# PowerSheet1.net
KiCad netlist of a schematic drawn in Altium Designer
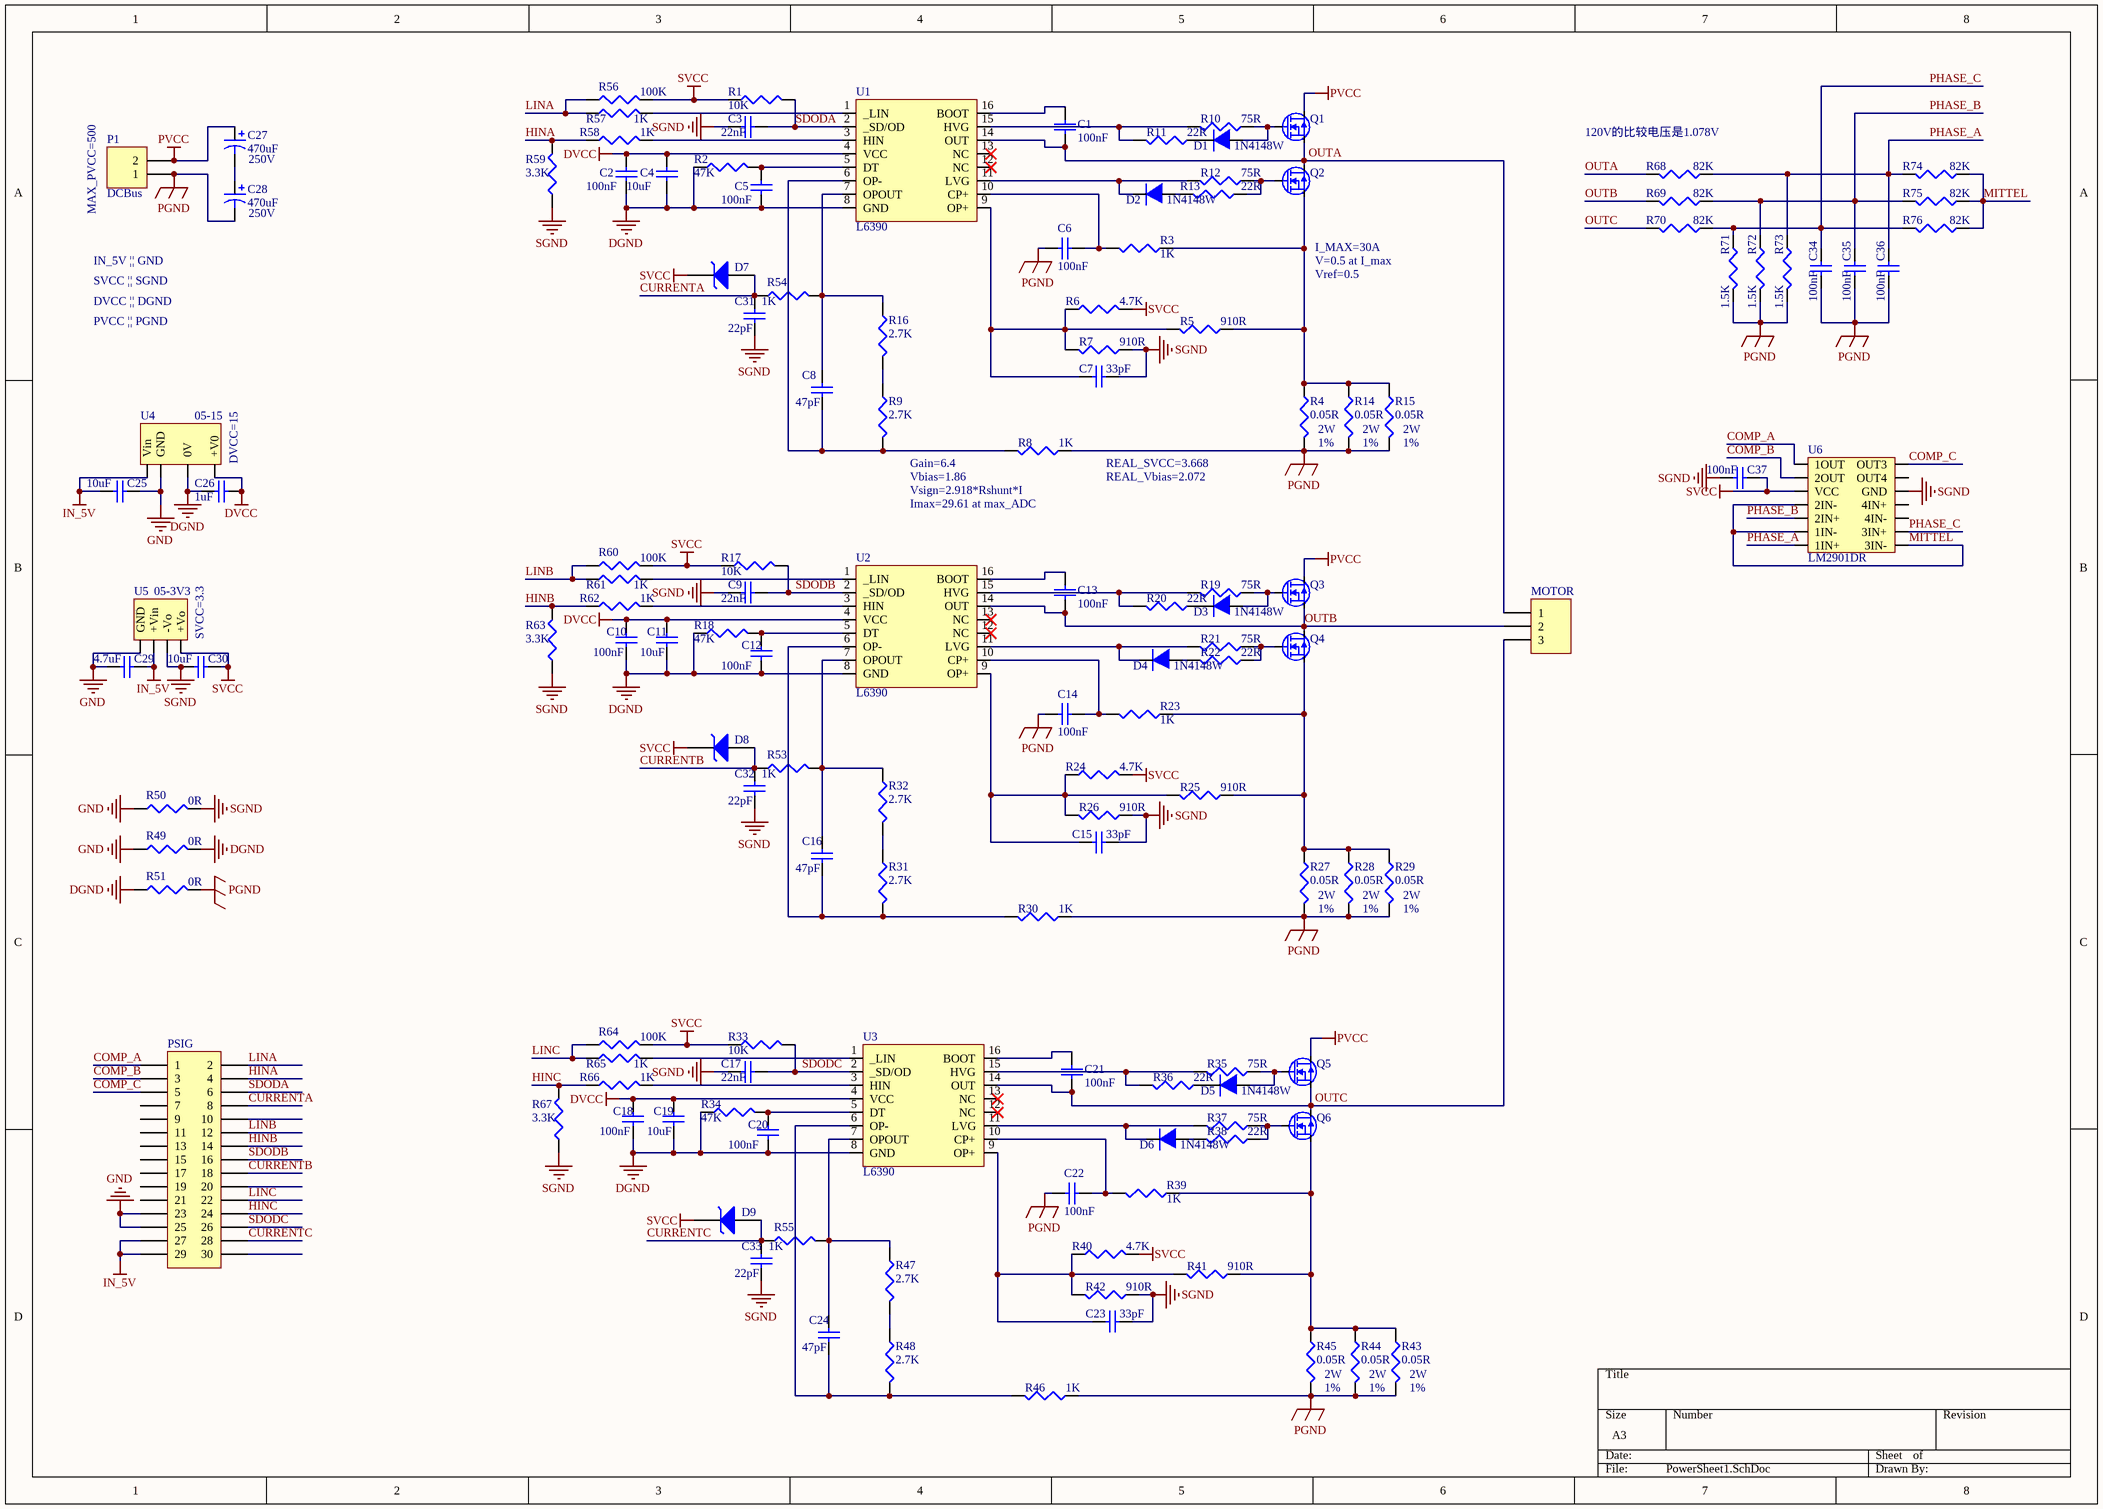
[diagram p0: PowerSheet1.SchDoc]

(export (version "E")
  (design (tool "Eeschema 10.0.6"))
  (components
    (comp (ref "C1")
      (value "100nF")
      (footprint "LC-1210_C")
      (description "Capacitor (Semiconductor SIM Model)")
      (fields (field (name "Comment") "Cap Semi") (field (name "PUBLISHER") "Altium Limited"))
      (libsource (lib "Miscellaneous Devices") (part "Cap Semi"))
    )
    (comp (ref "C2")
      (value "100nF")
      (footprint "LC-0805_C")
      (description "Capacitor (Semiconductor SIM Model)")
      (fields (field (name "Comment") "Cap Semi") (field (name "PUBLISHER") "Altium Limited"))
      (libsource (lib "Miscellaneous Devices") (part "Cap Semi"))
    )
    (comp (ref "C3")
      (value "22nF")
      (footprint "LC-0805_C")
      (description "Capacitor (Semiconductor SIM Model)")
      (fields (field (name "Comment") "Cap Semi") (field (name "PUBLISHER") "Altium Limited"))
      (libsource (lib "Miscellaneous Devices") (part "Cap Semi"))
    )
    (comp (ref "C4")
      (value "10uF")
      (footprint "LC-0805_C")
      (description "Capacitor (Semiconductor SIM Model)")
      (fields (field (name "Comment") "Cap Semi") (field (name "PUBLISHER") "Altium Limited"))
      (libsource (lib "Miscellaneous Devices") (part "Cap Semi"))
    )
    (comp (ref "C5")
      (value "100nF")
      (footprint "LC-0805_C")
      (description "Capacitor (Semiconductor SIM Model)")
      (fields (field (name "Comment") "Cap Semi") (field (name "PUBLISHER") "Altium Limited"))
      (libsource (lib "Miscellaneous Devices") (part "Cap Semi"))
    )
    (comp (ref "C6")
      (value "100nF")
      (footprint "LC-0805_C")
      (description "Capacitor (Semiconductor SIM Model)")
      (fields (field (name "Comment") "Cap Semi") (field (name "PUBLISHER") "Altium Limited"))
      (libsource (lib "Miscellaneous Devices") (part "Cap Semi"))
    )
    (comp (ref "C7")
      (value "33pF")
      (footprint "LC-0805_C")
      (description "Capacitor (Semiconductor SIM Model)")
      (fields (field (name "Comment") "Cap Semi") (field (name "PUBLISHER") "Altium Limited"))
      (libsource (lib "Miscellaneous Devices") (part "Cap Semi"))
    )
    (comp (ref "C8")
      (value "47pF")
      (footprint "LC-0805_C")
      (description "Capacitor (Semiconductor SIM Model)")
      (fields (field (name "Comment") "Cap Semi") (field (name "PUBLISHER") "Altium Limited"))
      (libsource (lib "Miscellaneous Devices") (part "Cap Semi"))
    )
    (comp (ref "C9")
      (value "22nF")
      (footprint "LC-0805_C")
      (description "Capacitor (Semiconductor SIM Model)")
      (fields (field (name "Comment") "Cap Semi") (field (name "PUBLISHER") "Altium Limited"))
      (libsource (lib "Miscellaneous Devices") (part "Cap Semi"))
    )
    (comp (ref "C10")
      (value "100nF")
      (footprint "LC-0805_C")
      (description "Capacitor (Semiconductor SIM Model)")
      (fields (field (name "Comment") "Cap Semi") (field (name "PUBLISHER") "Altium Limited"))
      (libsource (lib "Miscellaneous Devices") (part "Cap Semi"))
    )
    (comp (ref "C11")
      (value "10uF")
      (footprint "LC-0805_C")
      (description "Capacitor (Semiconductor SIM Model)")
      (fields (field (name "Comment") "Cap Semi") (field (name "PUBLISHER") "Altium Limited"))
      (libsource (lib "Miscellaneous Devices") (part "Cap Semi"))
    )
    (comp (ref "C12")
      (value "100nF")
      (footprint "LC-0805_C")
      (description "Capacitor (Semiconductor SIM Model)")
      (fields (field (name "Comment") "Cap Semi") (field (name "PUBLISHER") "Altium Limited"))
      (libsource (lib "Miscellaneous Devices") (part "Cap Semi"))
    )
    (comp (ref "C13")
      (value "100nF")
      (footprint "LC-1210_C")
      (description "Capacitor (Semiconductor SIM Model)")
      (fields (field (name "Comment") "Cap Semi") (field (name "PUBLISHER") "Altium Limited"))
      (libsource (lib "Miscellaneous Devices") (part "Cap Semi"))
    )
    (comp (ref "C14")
      (value "100nF")
      (footprint "LC-0805_C")
      (description "Capacitor (Semiconductor SIM Model)")
      (fields (field (name "Comment") "Cap Semi") (field (name "PUBLISHER") "Altium Limited"))
      (libsource (lib "Miscellaneous Devices") (part "Cap Semi"))
    )
    (comp (ref "C15")
      (value "33pF")
      (footprint "LC-0805_C")
      (description "Capacitor (Semiconductor SIM Model)")
      (fields (field (name "Comment") "Cap Semi") (field (name "PUBLISHER") "Altium Limited"))
      (libsource (lib "Miscellaneous Devices") (part "Cap Semi"))
    )
    (comp (ref "C16")
      (value "47pF")
      (footprint "LC-0805_C")
      (description "Capacitor (Semiconductor SIM Model)")
      (fields (field (name "Comment") "Cap Semi") (field (name "PUBLISHER") "Altium Limited"))
      (libsource (lib "Miscellaneous Devices") (part "Cap Semi"))
    )
    (comp (ref "C17")
      (value "22nF")
      (footprint "LC-0805_C")
      (description "Capacitor (Semiconductor SIM Model)")
      (fields (field (name "Comment") "Cap Semi") (field (name "PUBLISHER") "Altium Limited"))
      (libsource (lib "Miscellaneous Devices") (part "Cap Semi"))
    )
    (comp (ref "C18")
      (value "100nF")
      (footprint "LC-0805_C")
      (description "Capacitor (Semiconductor SIM Model)")
      (fields (field (name "Comment") "Cap Semi") (field (name "PUBLISHER") "Altium Limited"))
      (libsource (lib "Miscellaneous Devices") (part "Cap Semi"))
    )
    (comp (ref "C19")
      (value "10uF")
      (footprint "LC-0805_C")
      (description "Capacitor (Semiconductor SIM Model)")
      (fields (field (name "Comment") "Cap Semi") (field (name "PUBLISHER") "Altium Limited"))
      (libsource (lib "Miscellaneous Devices") (part "Cap Semi"))
    )
    (comp (ref "C20")
      (value "100nF")
      (footprint "LC-0805_C")
      (description "Capacitor (Semiconductor SIM Model)")
      (fields (field (name "Comment") "Cap Semi") (field (name "PUBLISHER") "Altium Limited"))
      (libsource (lib "Miscellaneous Devices") (part "Cap Semi"))
    )
    (comp (ref "C21")
      (value "100nF")
      (footprint "LC-1210_C")
      (description "Capacitor (Semiconductor SIM Model)")
      (fields (field (name "Comment") "Cap Semi") (field (name "PUBLISHER") "Altium Limited"))
      (libsource (lib "Miscellaneous Devices") (part "Cap Semi"))
    )
    (comp (ref "C22")
      (value "100nF")
      (footprint "LC-0805_C")
      (description "Capacitor (Semiconductor SIM Model)")
      (fields (field (name "Comment") "Cap Semi") (field (name "PUBLISHER") "Altium Limited"))
      (libsource (lib "Miscellaneous Devices") (part "Cap Semi"))
    )
    (comp (ref "C23")
      (value "33pF")
      (footprint "LC-0805_C")
      (description "Capacitor (Semiconductor SIM Model)")
      (fields (field (name "Comment") "Cap Semi") (field (name "PUBLISHER") "Altium Limited"))
      (libsource (lib "Miscellaneous Devices") (part "Cap Semi"))
    )
    (comp (ref "C24")
      (value "47pF")
      (footprint "LC-0805_C")
      (description "Capacitor (Semiconductor SIM Model)")
      (fields (field (name "Comment") "Cap Semi") (field (name "PUBLISHER") "Altium Limited"))
      (libsource (lib "Miscellaneous Devices") (part "Cap Semi"))
    )
    (comp (ref "C25")
      (value "10uF")
      (footprint "LC-0805_C")
      (description "Capacitor (Semiconductor SIM Model)")
      (fields (field (name "Comment") "Cap Semi") (field (name "PUBLISHER") "Altium Limited"))
      (libsource (lib "Miscellaneous Devices") (part "Cap Semi"))
    )
    (comp (ref "C26")
      (value "1uF")
      (footprint "LC-0805_C")
      (description "Capacitor (Semiconductor SIM Model)")
      (fields (field (name "Comment") "Cap Semi") (field (name "PUBLISHER") "Altium Limited"))
      (libsource (lib "Miscellaneous Devices") (part "Cap Semi"))
    )
    (comp (ref "C27")
      (value "470uF")
      (footprint "CAPACITORS")
      (description "Polarized Capacitor (Radial)")
      (fields
        (field (name "VOLTAGE") "250V")
        (field (name "Comment") "Cap Pol1")
        (field (name "PUBLISHER") "Altium Limited")
      )
      (libsource (lib "Miscellaneous Devices") (part "Cap Pol1"))
    )
    (comp (ref "C28")
      (value "470uF")
      (footprint "CAPACITORS")
      (description "Polarized Capacitor (Radial)")
      (fields
        (field (name "VOLTAGE") "250V")
        (field (name "Comment") "Cap Pol1")
        (field (name "PUBLISHER") "Altium Limited")
      )
      (libsource (lib "Miscellaneous Devices") (part "Cap Pol1"))
    )
    (comp (ref "C29")
      (value "4.7uF")
      (footprint "LC-0805_C")
      (description "Capacitor (Semiconductor SIM Model)")
      (fields (field (name "Comment") "Cap Semi") (field (name "PUBLISHER") "Altium Limited"))
      (libsource (lib "Miscellaneous Devices") (part "Cap Semi"))
    )
    (comp (ref "C30")
      (value "10uF")
      (footprint "LC-0805_C")
      (description "Capacitor (Semiconductor SIM Model)")
      (fields (field (name "Comment") "Cap Semi") (field (name "PUBLISHER") "Altium Limited"))
      (libsource (lib "Miscellaneous Devices") (part "Cap Semi"))
    )
    (comp (ref "C31")
      (value "22pF")
      (footprint "LC-0805_C")
      (description "Capacitor (Semiconductor SIM Model)")
      (fields (field (name "Comment") "Cap Semi") (field (name "PUBLISHER") "Altium Limited"))
      (libsource (lib "Miscellaneous Devices") (part "Cap Semi"))
    )
    (comp (ref "C32")
      (value "22pF")
      (footprint "LC-0805_C")
      (description "Capacitor (Semiconductor SIM Model)")
      (fields (field (name "Comment") "Cap Semi") (field (name "PUBLISHER") "Altium Limited"))
      (libsource (lib "Miscellaneous Devices") (part "Cap Semi"))
    )
    (comp (ref "C33")
      (value "22pF")
      (footprint "LC-0805_C")
      (description "Capacitor (Semiconductor SIM Model)")
      (fields (field (name "Comment") "Cap Semi") (field (name "PUBLISHER") "Altium Limited"))
      (libsource (lib "Miscellaneous Devices") (part "Cap Semi"))
    )
    (comp (ref "C34")
      (value "100nF")
      (footprint "LC-0805_C")
      (description "Capacitor (Semiconductor SIM Model)")
      (fields (field (name "Comment") "Cap Semi") (field (name "PUBLISHER") "Altium Limited"))
      (libsource (lib "Miscellaneous Devices") (part "Cap Semi"))
    )
    (comp (ref "C35")
      (value "100nF")
      (footprint "LC-0805_C")
      (description "Capacitor (Semiconductor SIM Model)")
      (fields (field (name "Comment") "Cap Semi") (field (name "PUBLISHER") "Altium Limited"))
      (libsource (lib "Miscellaneous Devices") (part "Cap Semi"))
    )
    (comp (ref "C36")
      (value "100nF")
      (footprint "LC-0805_C")
      (description "Capacitor (Semiconductor SIM Model)")
      (fields (field (name "Comment") "Cap Semi") (field (name "PUBLISHER") "Altium Limited"))
      (libsource (lib "Miscellaneous Devices") (part "Cap Semi"))
    )
    (comp (ref "C37")
      (value "100nF")
      (footprint "LC-0805_C")
      (description "Capacitor (Semiconductor SIM Model)")
      (fields (field (name "Comment") "Cap Semi") (field (name "PUBLISHER") "Altium Limited"))
      (libsource (lib "Miscellaneous Devices") (part "Cap Semi"))
    )
    (comp (ref "D1")
      (value "1N4148W")
      (footprint "SOD-123-D-IPC")
      (description "1N4148WS")
      (libsource (lib "MySchlib") (part "1N4148"))
    )
    (comp (ref "D2")
      (value "1N4148W")
      (footprint "SOD-123-D-IPC")
      (description "1N4148WS")
      (libsource (lib "MySchlib") (part "1N4148"))
    )
    (comp (ref "D3")
      (value "1N4148W")
      (footprint "SOD-123-D-IPC")
      (description "1N4148WS")
      (libsource (lib "MySchlib") (part "1N4148"))
    )
    (comp (ref "D4")
      (value "1N4148W")
      (footprint "SOD-123-D-IPC")
      (description "1N4148WS")
      (libsource (lib "MySchlib") (part "1N4148"))
    )
    (comp (ref "D5")
      (value "1N4148W")
      (footprint "SOD-123-D-IPC")
      (description "1N4148WS")
      (libsource (lib "MySchlib") (part "1N4148"))
    )
    (comp (ref "D6")
      (value "1N4148W")
      (footprint "SOD-123-D-IPC")
      (description "1N4148WS")
      (libsource (lib "MySchlib") (part "1N4148"))
    )
    (comp (ref "D7")
      (value "D Schottky")
      (footprint "MELF3416N")
      (description "TMMBAT48FILM")
      (libsource (lib "MySchlib") (part "D Schottky"))
    )
    (comp (ref "D8")
      (value "D Schottky")
      (footprint "MELF3416N")
      (description "TMMBAT48FILM")
      (libsource (lib "MySchlib") (part "D Schottky"))
    )
    (comp (ref "D9")
      (value "D Schottky")
      (footprint "MELF3416N")
      (description "TMMBAT48FILM")
      (libsource (lib "MySchlib") (part "D Schottky"))
    )
    (comp (ref "MOTOR")
      (value "Header 3")
      (footprint "MKDS5/3-9.5")
      (description "Header, 3-Pin")
      (fields (field (name "PUBLISHER") "Altium Limited"))
      (libsource (lib "Miscellaneous Connectors") (part "Header 3"))
    )
    (comp (ref "P1")
      (value "DCBus")
      (footprint "MKDS5/2-9.5 - duplicate")
      (description "Header, 2-Pin")
      (fields (field (name "PUBLISHER") "Altium Limited"))
      (libsource (lib "Miscellaneous Connectors") (part "Header 2"))
    )
    (comp (ref "PSIG")
      (value "Header 15X2")
      (footprint "HDR2X15")
      (description "Header, 15-Pin, Dual row")
      (fields (field (name "PUBLISHER") "Altium Limited"))
      (libsource (lib "Miscellaneous Connectors") (part "Header 15X2"))
    )
    (comp (ref "Q1")
      (value "MOSFET-N")
      (footprint "DPAK254P1525X450-3N-IPB60R080P7")
      (description "IPB60R080P7")
      (libsource (lib "MySchlib") (part "MOSFET-N"))
    )
    (comp (ref "Q2")
      (value "MOSFET-N")
      (footprint "DPAK254P1525X450-3N-IPB60R080P7")
      (description "IPB60R080P7")
      (libsource (lib "MySchlib") (part "MOSFET-N"))
    )
    (comp (ref "Q3")
      (value "MOSFET-N")
      (footprint "DPAK254P1525X450-3N-IPB60R080P7")
      (description "IPB60R080P7")
      (libsource (lib "MySchlib") (part "MOSFET-N"))
    )
    (comp (ref "Q4")
      (value "MOSFET-N")
      (footprint "DPAK254P1525X450-3N-IPB60R080P7")
      (description "IPB60R080P7")
      (libsource (lib "MySchlib") (part "MOSFET-N"))
    )
    (comp (ref "Q5")
      (value "MOSFET-N")
      (footprint "DPAK254P1525X450-3N-IPB60R080P7")
      (description "IPB60R080P7")
      (libsource (lib "MySchlib") (part "MOSFET-N"))
    )
    (comp (ref "Q6")
      (value "MOSFET-N")
      (footprint "DPAK254P1525X450-3N-IPB60R080P7")
      (description "IPB60R080P7")
      (libsource (lib "MySchlib") (part "MOSFET-N"))
    )
    (comp (ref "R1")
      (value "10K")
      (footprint "LC-0805_R")
      (description "Resistor")
      (fields (field (name "Comment") "Res3") (field (name "PUBLISHER") "Altium Limited"))
      (libsource (lib "Miscellaneous Devices") (part "Res3"))
    )
    (comp (ref "R2")
      (value "47K")
      (footprint "LC-0805_R")
      (description "Resistor")
      (fields (field (name "Comment") "Res3") (field (name "PUBLISHER") "Altium Limited"))
      (libsource (lib "Miscellaneous Devices") (part "Res3"))
    )
    (comp (ref "R3")
      (value "1K")
      (footprint "LC-0805_R")
      (description "Resistor")
      (fields (field (name "Comment") "Res3") (field (name "PUBLISHER") "Altium Limited"))
      (libsource (lib "Miscellaneous Devices") (part "Res3"))
    )
    (comp (ref "R4")
      (value "0.05R")
      (footprint "12Z-2010")
      (description "Resistor")
      (fields
        (field (name "POWER") "2W")
        (field (name "PRECISION") "1%")
        (field (name "Comment") "Res3")
        (field (name "PUBLISHER") "Altium Limited")
      )
      (libsource (lib "Miscellaneous Devices") (part "Res3"))
    )
    (comp (ref "R5")
      (value "910R")
      (footprint "LC-0805_R")
      (description "Resistor")
      (fields (field (name "Comment") "Res3") (field (name "PUBLISHER") "Altium Limited"))
      (libsource (lib "Miscellaneous Devices") (part "Res3"))
    )
    (comp (ref "R6")
      (value "4.7K")
      (footprint "LC-0805_R")
      (description "Resistor")
      (fields (field (name "Comment") "Res3") (field (name "PUBLISHER") "Altium Limited"))
      (libsource (lib "Miscellaneous Devices") (part "Res3"))
    )
    (comp (ref "R7")
      (value "910R")
      (footprint "LC-0805_R")
      (description "Resistor")
      (fields (field (name "Comment") "Res3") (field (name "PUBLISHER") "Altium Limited"))
      (libsource (lib "Miscellaneous Devices") (part "Res3"))
    )
    (comp (ref "R8")
      (value "1K")
      (footprint "LC-0805_R")
      (description "Resistor")
      (fields (field (name "Comment") "Res3") (field (name "PUBLISHER") "Altium Limited"))
      (libsource (lib "Miscellaneous Devices") (part "Res3"))
    )
    (comp (ref "R9")
      (value "2.7K")
      (footprint "LC-0805_R")
      (description "Resistor")
      (fields (field (name "Comment") "Res3") (field (name "PUBLISHER") "Altium Limited"))
      (libsource (lib "Miscellaneous Devices") (part "Res3"))
    )
    (comp (ref "R10")
      (value "75R")
      (footprint "LC-0805_R")
      (description "Resistor")
      (fields (field (name "Comment") "Res3") (field (name "PUBLISHER") "Altium Limited"))
      (libsource (lib "Miscellaneous Devices") (part "Res3"))
    )
    (comp (ref "R11")
      (value "22R")
      (footprint "LC-0805_R")
      (description "Resistor")
      (fields (field (name "Comment") "Res3") (field (name "PUBLISHER") "Altium Limited"))
      (libsource (lib "Miscellaneous Devices") (part "Res3"))
    )
    (comp (ref "R12")
      (value "75R")
      (footprint "LC-0805_R")
      (description "Resistor")
      (fields (field (name "Comment") "Res3") (field (name "PUBLISHER") "Altium Limited"))
      (libsource (lib "Miscellaneous Devices") (part "Res3"))
    )
    (comp (ref "R13")
      (value "22R")
      (footprint "LC-0805_R")
      (description "Resistor")
      (fields (field (name "Comment") "Res3") (field (name "PUBLISHER") "Altium Limited"))
      (libsource (lib "Miscellaneous Devices") (part "Res3"))
    )
    (comp (ref "R14")
      (value "0.05R")
      (footprint "12Z-2010")
      (description "Resistor")
      (fields
        (field (name "POWER") "2W")
        (field (name "PRECISION") "1%")
        (field (name "Comment") "Res3")
        (field (name "PUBLISHER") "Altium Limited")
      )
      (libsource (lib "Miscellaneous Devices") (part "Res3"))
    )
    (comp (ref "R15")
      (value "0.05R")
      (footprint "12Z-2010")
      (description "Resistor")
      (fields
        (field (name "POWER") "2W")
        (field (name "PRECISION") "1%")
        (field (name "Comment") "Res3")
        (field (name "PUBLISHER") "Altium Limited")
      )
      (libsource (lib "Miscellaneous Devices") (part "Res3"))
    )
    (comp (ref "R16")
      (value "2.7K")
      (footprint "LC-0805_R")
      (description "Resistor")
      (fields (field (name "Comment") "Res3") (field (name "PUBLISHER") "Altium Limited"))
      (libsource (lib "Miscellaneous Devices") (part "Res3"))
    )
    (comp (ref "R17")
      (value "10K")
      (footprint "LC-0805_R")
      (description "Resistor")
      (fields (field (name "Comment") "Res3") (field (name "PUBLISHER") "Altium Limited"))
      (libsource (lib "Miscellaneous Devices") (part "Res3"))
    )
    (comp (ref "R18")
      (value "47K")
      (footprint "LC-0805_R")
      (description "Resistor")
      (fields (field (name "Comment") "Res3") (field (name "PUBLISHER") "Altium Limited"))
      (libsource (lib "Miscellaneous Devices") (part "Res3"))
    )
    (comp (ref "R19")
      (value "75R")
      (footprint "LC-0805_R")
      (description "Resistor")
      (fields (field (name "Comment") "Res3") (field (name "PUBLISHER") "Altium Limited"))
      (libsource (lib "Miscellaneous Devices") (part "Res3"))
    )
    (comp (ref "R20")
      (value "22R")
      (footprint "LC-0805_R")
      (description "Resistor")
      (fields (field (name "Comment") "Res3") (field (name "PUBLISHER") "Altium Limited"))
      (libsource (lib "Miscellaneous Devices") (part "Res3"))
    )
    (comp (ref "R21")
      (value "75R")
      (footprint "LC-0805_R")
      (description "Resistor")
      (fields (field (name "Comment") "Res3") (field (name "PUBLISHER") "Altium Limited"))
      (libsource (lib "Miscellaneous Devices") (part "Res3"))
    )
    (comp (ref "R22")
      (value "22R")
      (footprint "LC-0805_R")
      (description "Resistor")
      (fields (field (name "Comment") "Res3") (field (name "PUBLISHER") "Altium Limited"))
      (libsource (lib "Miscellaneous Devices") (part "Res3"))
    )
    (comp (ref "R23")
      (value "1K")
      (footprint "LC-0805_R")
      (description "Resistor")
      (fields (field (name "Comment") "Res3") (field (name "PUBLISHER") "Altium Limited"))
      (libsource (lib "Miscellaneous Devices") (part "Res3"))
    )
    (comp (ref "R24")
      (value "4.7K")
      (footprint "LC-0805_R")
      (description "Resistor")
      (fields (field (name "Comment") "Res3") (field (name "PUBLISHER") "Altium Limited"))
      (libsource (lib "Miscellaneous Devices") (part "Res3"))
    )
    (comp (ref "R25")
      (value "910R")
      (footprint "LC-0805_R")
      (description "Resistor")
      (fields (field (name "Comment") "Res3") (field (name "PUBLISHER") "Altium Limited"))
      (libsource (lib "Miscellaneous Devices") (part "Res3"))
    )
    (comp (ref "R26")
      (value "910R")
      (footprint "LC-0805_R")
      (description "Resistor")
      (fields (field (name "Comment") "Res3") (field (name "PUBLISHER") "Altium Limited"))
      (libsource (lib "Miscellaneous Devices") (part "Res3"))
    )
    (comp (ref "R27")
      (value "0.05R")
      (footprint "12Z-2010")
      (description "Resistor")
      (fields
        (field (name "POWER") "2W")
        (field (name "PRECISION") "1%")
        (field (name "Comment") "Res3")
        (field (name "PUBLISHER") "Altium Limited")
      )
      (libsource (lib "Miscellaneous Devices") (part "Res3"))
    )
    (comp (ref "R28")
      (value "0.05R")
      (footprint "12Z-2010")
      (description "Resistor")
      (fields
        (field (name "POWER") "2W")
        (field (name "PRECISION") "1%")
        (field (name "Comment") "Res3")
        (field (name "PUBLISHER") "Altium Limited")
      )
      (libsource (lib "Miscellaneous Devices") (part "Res3"))
    )
    (comp (ref "R29")
      (value "0.05R")
      (footprint "12Z-2010")
      (description "Resistor")
      (fields
        (field (name "POWER") "2W")
        (field (name "PRECISION") "1%")
        (field (name "Comment") "Res3")
        (field (name "PUBLISHER") "Altium Limited")
      )
      (libsource (lib "Miscellaneous Devices") (part "Res3"))
    )
    (comp (ref "R30")
      (value "1K")
      (footprint "LC-0805_R")
      (description "Resistor")
      (fields (field (name "Comment") "Res3") (field (name "PUBLISHER") "Altium Limited"))
      (libsource (lib "Miscellaneous Devices") (part "Res3"))
    )
    (comp (ref "R31")
      (value "2.7K")
      (footprint "LC-0805_R")
      (description "Resistor")
      (fields (field (name "Comment") "Res3") (field (name "PUBLISHER") "Altium Limited"))
      (libsource (lib "Miscellaneous Devices") (part "Res3"))
    )
    (comp (ref "R32")
      (value "2.7K")
      (footprint "LC-0805_R")
      (description "Resistor")
      (fields (field (name "Comment") "Res3") (field (name "PUBLISHER") "Altium Limited"))
      (libsource (lib "Miscellaneous Devices") (part "Res3"))
    )
    (comp (ref "R33")
      (value "10K")
      (footprint "LC-0805_R")
      (description "Resistor")
      (fields (field (name "Comment") "Res3") (field (name "PUBLISHER") "Altium Limited"))
      (libsource (lib "Miscellaneous Devices") (part "Res3"))
    )
    (comp (ref "R34")
      (value "47K")
      (footprint "LC-0805_R")
      (description "Resistor")
      (fields (field (name "Comment") "Res3") (field (name "PUBLISHER") "Altium Limited"))
      (libsource (lib "Miscellaneous Devices") (part "Res3"))
    )
    (comp (ref "R35")
      (value "75R")
      (footprint "LC-0805_R")
      (description "Resistor")
      (fields (field (name "Comment") "Res3") (field (name "PUBLISHER") "Altium Limited"))
      (libsource (lib "Miscellaneous Devices") (part "Res3"))
    )
    (comp (ref "R36")
      (value "22R")
      (footprint "LC-0805_R")
      (description "Resistor")
      (fields (field (name "Comment") "Res3") (field (name "PUBLISHER") "Altium Limited"))
      (libsource (lib "Miscellaneous Devices") (part "Res3"))
    )
    (comp (ref "R37")
      (value "75R")
      (footprint "LC-0805_R")
      (description "Resistor")
      (fields (field (name "Comment") "Res3") (field (name "PUBLISHER") "Altium Limited"))
      (libsource (lib "Miscellaneous Devices") (part "Res3"))
    )
    (comp (ref "R38")
      (value "22R")
      (footprint "LC-0805_R")
      (description "Resistor")
      (fields (field (name "Comment") "Res3") (field (name "PUBLISHER") "Altium Limited"))
      (libsource (lib "Miscellaneous Devices") (part "Res3"))
    )
    (comp (ref "R39")
      (value "1K")
      (footprint "LC-0805_R")
      (description "Resistor")
      (fields (field (name "Comment") "Res3") (field (name "PUBLISHER") "Altium Limited"))
      (libsource (lib "Miscellaneous Devices") (part "Res3"))
    )
    (comp (ref "R40")
      (value "4.7K")
      (footprint "LC-0805_R")
      (description "Resistor")
      (fields (field (name "Comment") "Res3") (field (name "PUBLISHER") "Altium Limited"))
      (libsource (lib "Miscellaneous Devices") (part "Res3"))
    )
    (comp (ref "R41")
      (value "910R")
      (footprint "LC-0805_R")
      (description "Resistor")
      (fields (field (name "Comment") "Res3") (field (name "PUBLISHER") "Altium Limited"))
      (libsource (lib "Miscellaneous Devices") (part "Res3"))
    )
    (comp (ref "R42")
      (value "910R")
      (footprint "LC-0805_R")
      (description "Resistor")
      (fields (field (name "Comment") "Res3") (field (name "PUBLISHER") "Altium Limited"))
      (libsource (lib "Miscellaneous Devices") (part "Res3"))
    )
    (comp (ref "R43")
      (value "0.05R")
      (footprint "12Z-2010")
      (description "Resistor")
      (fields
        (field (name "POWER") "2W")
        (field (name "PRECISION") "1%")
        (field (name "Comment") "Res3")
        (field (name "PUBLISHER") "Altium Limited")
      )
      (libsource (lib "Miscellaneous Devices") (part "Res3"))
    )
    (comp (ref "R44")
      (value "0.05R")
      (footprint "12Z-2010")
      (description "Resistor")
      (fields
        (field (name "POWER") "2W")
        (field (name "PRECISION") "1%")
        (field (name "Comment") "Res3")
        (field (name "PUBLISHER") "Altium Limited")
      )
      (libsource (lib "Miscellaneous Devices") (part "Res3"))
    )
    (comp (ref "R45")
      (value "0.05R")
      (footprint "12Z-2010")
      (description "Resistor")
      (fields
        (field (name "POWER") "2W")
        (field (name "PRECISION") "1%")
        (field (name "Comment") "Res3")
        (field (name "PUBLISHER") "Altium Limited")
      )
      (libsource (lib "Miscellaneous Devices") (part "Res3"))
    )
    (comp (ref "R46")
      (value "1K")
      (footprint "LC-0805_R")
      (description "Resistor")
      (fields (field (name "Comment") "Res3") (field (name "PUBLISHER") "Altium Limited"))
      (libsource (lib "Miscellaneous Devices") (part "Res3"))
    )
    (comp (ref "R47")
      (value "2.7K")
      (footprint "LC-0805_R")
      (description "Resistor")
      (fields (field (name "Comment") "Res3") (field (name "PUBLISHER") "Altium Limited"))
      (libsource (lib "Miscellaneous Devices") (part "Res3"))
    )
    (comp (ref "R48")
      (value "2.7K")
      (footprint "LC-0805_R")
      (description "Resistor")
      (fields (field (name "Comment") "Res3") (field (name "PUBLISHER") "Altium Limited"))
      (libsource (lib "Miscellaneous Devices") (part "Res3"))
    )
    (comp (ref "R49")
      (value "0R")
      (footprint "LC-0805_R")
      (description "Resistor")
      (fields (field (name "Comment") "Res3") (field (name "PUBLISHER") "Altium Limited"))
      (libsource (lib "Miscellaneous Devices") (part "Res3"))
    )
    (comp (ref "R50")
      (value "0R")
      (footprint "LC-0805_R")
      (description "Resistor")
      (fields (field (name "Comment") "Res3") (field (name "PUBLISHER") "Altium Limited"))
      (libsource (lib "Miscellaneous Devices") (part "Res3"))
    )
    (comp (ref "R51")
      (value "0R")
      (footprint "LC-0805_R")
      (description "Resistor")
      (fields (field (name "Comment") "Res3") (field (name "PUBLISHER") "Altium Limited"))
      (libsource (lib "Miscellaneous Devices") (part "Res3"))
    )
    (comp (ref "R53")
      (value "1K")
      (footprint "LC-0805_R")
      (description "Resistor")
      (fields (field (name "Comment") "Res3") (field (name "PUBLISHER") "Altium Limited"))
      (libsource (lib "Miscellaneous Devices") (part "Res3"))
    )
    (comp (ref "R54")
      (value "1K")
      (footprint "LC-0805_R")
      (description "Resistor")
      (fields (field (name "Comment") "Res3") (field (name "PUBLISHER") "Altium Limited"))
      (libsource (lib "Miscellaneous Devices") (part "Res3"))
    )
    (comp (ref "R55")
      (value "1K")
      (footprint "LC-0805_R")
      (description "Resistor")
      (fields (field (name "Comment") "Res3") (field (name "PUBLISHER") "Altium Limited"))
      (libsource (lib "Miscellaneous Devices") (part "Res3"))
    )
    (comp (ref "R56")
      (value "100K")
      (footprint "LC-0805_R")
      (description "Resistor")
      (fields (field (name "Comment") "Res3") (field (name "PUBLISHER") "Altium Limited"))
      (libsource (lib "Miscellaneous Devices") (part "Res3"))
    )
    (comp (ref "R57")
      (value "1K")
      (footprint "LC-0805_R")
      (description "Resistor")
      (fields (field (name "Comment") "Res3") (field (name "PUBLISHER") "Altium Limited"))
      (libsource (lib "Miscellaneous Devices") (part "Res3"))
    )
    (comp (ref "R58")
      (value "1K")
      (footprint "LC-0805_R")
      (description "Resistor")
      (fields (field (name "Comment") "Res3") (field (name "PUBLISHER") "Altium Limited"))
      (libsource (lib "Miscellaneous Devices") (part "Res3"))
    )
    (comp (ref "R59")
      (value "3.3K")
      (footprint "LC-0805_R")
      (description "Resistor")
      (fields (field (name "Comment") "Res3") (field (name "PUBLISHER") "Altium Limited"))
      (libsource (lib "Miscellaneous Devices") (part "Res3"))
    )
    (comp (ref "R60")
      (value "100K")
      (footprint "LC-0805_R")
      (description "Resistor")
      (fields (field (name "Comment") "Res3") (field (name "PUBLISHER") "Altium Limited"))
      (libsource (lib "Miscellaneous Devices") (part "Res3"))
    )
    (comp (ref "R61")
      (value "1K")
      (footprint "LC-0805_R")
      (description "Resistor")
      (fields (field (name "Comment") "Res3") (field (name "PUBLISHER") "Altium Limited"))
      (libsource (lib "Miscellaneous Devices") (part "Res3"))
    )
    (comp (ref "R62")
      (value "1K")
      (footprint "LC-0805_R")
      (description "Resistor")
      (fields (field (name "Comment") "Res3") (field (name "PUBLISHER") "Altium Limited"))
      (libsource (lib "Miscellaneous Devices") (part "Res3"))
    )
    (comp (ref "R63")
      (value "3.3K")
      (footprint "LC-0805_R")
      (description "Resistor")
      (fields (field (name "Comment") "Res3") (field (name "PUBLISHER") "Altium Limited"))
      (libsource (lib "Miscellaneous Devices") (part "Res3"))
    )
    (comp (ref "R64")
      (value "100K")
      (footprint "LC-0805_R")
      (description "Resistor")
      (fields (field (name "Comment") "Res3") (field (name "PUBLISHER") "Altium Limited"))
      (libsource (lib "Miscellaneous Devices") (part "Res3"))
    )
    (comp (ref "R65")
      (value "1K")
      (footprint "LC-0805_R")
      (description "Resistor")
      (fields (field (name "Comment") "Res3") (field (name "PUBLISHER") "Altium Limited"))
      (libsource (lib "Miscellaneous Devices") (part "Res3"))
    )
    (comp (ref "R66")
      (value "1K")
      (footprint "LC-0805_R")
      (description "Resistor")
      (fields (field (name "Comment") "Res3") (field (name "PUBLISHER") "Altium Limited"))
      (libsource (lib "Miscellaneous Devices") (part "Res3"))
    )
    (comp (ref "R67")
      (value "3.3K")
      (footprint "LC-0805_R")
      (description "Resistor")
      (fields (field (name "Comment") "Res3") (field (name "PUBLISHER") "Altium Limited"))
      (libsource (lib "Miscellaneous Devices") (part "Res3"))
    )
    (comp (ref "R68")
      (value "82K")
      (footprint "LC-0805_R")
      (description "Resistor")
      (fields (field (name "Comment") "Res3") (field (name "PUBLISHER") "Altium Limited"))
      (libsource (lib "Miscellaneous Devices") (part "Res3"))
    )
    (comp (ref "R69")
      (value "82K")
      (footprint "LC-0805_R")
      (description "Resistor")
      (fields (field (name "Comment") "Res3") (field (name "PUBLISHER") "Altium Limited"))
      (libsource (lib "Miscellaneous Devices") (part "Res3"))
    )
    (comp (ref "R70")
      (value "82K")
      (footprint "LC-0805_R")
      (description "Resistor")
      (fields (field (name "Comment") "Res3") (field (name "PUBLISHER") "Altium Limited"))
      (libsource (lib "Miscellaneous Devices") (part "Res3"))
    )
    (comp (ref "R71")
      (value "1.5K")
      (footprint "LC-0805_R")
      (description "Resistor")
      (fields (field (name "Comment") "Res3") (field (name "PUBLISHER") "Altium Limited"))
      (libsource (lib "Miscellaneous Devices") (part "Res3"))
    )
    (comp (ref "R72")
      (value "1.5K")
      (footprint "LC-0805_R")
      (description "Resistor")
      (fields (field (name "Comment") "Res3") (field (name "PUBLISHER") "Altium Limited"))
      (libsource (lib "Miscellaneous Devices") (part "Res3"))
    )
    (comp (ref "R73")
      (value "1.5K")
      (footprint "LC-0805_R")
      (description "Resistor")
      (fields (field (name "Comment") "Res3") (field (name "PUBLISHER") "Altium Limited"))
      (libsource (lib "Miscellaneous Devices") (part "Res3"))
    )
    (comp (ref "R74")
      (value "82K")
      (footprint "LC-0805_R")
      (description "Resistor")
      (fields (field (name "Comment") "Res3") (field (name "PUBLISHER") "Altium Limited"))
      (libsource (lib "Miscellaneous Devices") (part "Res3"))
    )
    (comp (ref "R75")
      (value "82K")
      (footprint "LC-0805_R")
      (description "Resistor")
      (fields (field (name "Comment") "Res3") (field (name "PUBLISHER") "Altium Limited"))
      (libsource (lib "Miscellaneous Devices") (part "Res3"))
    )
    (comp (ref "R76")
      (value "82K")
      (footprint "LC-0805_R")
      (description "Resistor")
      (fields (field (name "Comment") "Res3") (field (name "PUBLISHER") "Altium Limited"))
      (libsource (lib "Miscellaneous Devices") (part "Res3"))
    )
    (comp (ref "U1")
      (value "L6390")
      (footprint "SOIC127P660X175-16N")
      (description "ST High voltage high/low-side driver")
      (libsource (lib "MySchlib") (part "L6390"))
    )
    (comp (ref "U2")
      (value "L6390")
      (footprint "SOIC127P660X175-16N")
      (description "ST High voltage high/low-side driver")
      (libsource (lib "MySchlib") (part "L6390"))
    )
    (comp (ref "U3")
      (value "L6390")
      (footprint "SOIC127P660X175-16N")
      (description "ST High voltage high/low-side driver")
      (libsource (lib "MySchlib") (part "L6390"))
    )
    (comp (ref "U4")
      (value "05-15")
      (footprint "ZY0515IB/FS-1W")
      (description "ZY0515IB/FS-1W")
      (libsource (lib "MySchlib") (part "ZY0515IB/FS-1W"))
    )
    (comp (ref "U5")
      (value "05-3V3")
      (footprint "NN1-05S3V3A")
      (description "NN1-05S3V3A DC/DC")
      (libsource (lib "MySchlib") (part "NN1-05S3V3A"))
    )
    (comp (ref "U6")
      (value "LM2901DR")
      (footprint "LC-SOIC-14_150mil")
      (description "QUAD DIFFERENTIAL COMPARATORS")
      (libsource (lib "MySchlib") (part "LM2901DR"))
    )
  )
  (nets
    (net (code "1") (name "/COMP_A") (class "Default")
      (node (ref "PSIG") (pin "1") (pinfunction "1_1") (pintype "passive"))
      (node (ref "U6") (pin "1") (pinfunction "1OUT_1") (pintype "passive"))
    )
    (net (code "2") (name "/COMP_B") (class "Default")
      (node (ref "PSIG") (pin "3") (pinfunction "3_3") (pintype "passive"))
      (node (ref "U6") (pin "2") (pinfunction "2OUT_2") (pintype "passive"))
    )
    (net (code "3") (name "/COMP_C") (class "Default")
      (node (ref "PSIG") (pin "5") (pinfunction "5_5") (pintype "passive"))
      (node (ref "U6") (pin "14") (pinfunction "OUT3_14") (pintype "passive"))
    )
    (net (code "4") (name "/CURRENTA") (class "Default")
      (node (ref "C31") (pin "1") (pinfunction "1_1") (pintype "passive"))
      (node (ref "D7") (pin "1") (pinfunction "A_1") (pintype "passive"))
      (node (ref "PSIG") (pin "8") (pinfunction "8_8") (pintype "passive"))
      (node (ref "R54") (pin "1") (pinfunction "1_1") (pintype "passive"))
    )
    (net (code "5") (name "/CURRENTB") (class "Default")
      (node (ref "C32") (pin "1") (pinfunction "1_1") (pintype "passive"))
      (node (ref "D8") (pin "1") (pinfunction "A_1") (pintype "passive"))
      (node (ref "PSIG") (pin "18") (pinfunction "18_18") (pintype "passive"))
      (node (ref "R53") (pin "1") (pinfunction "1_1") (pintype "passive"))
    )
    (net (code "6") (name "/CURRENTC") (class "Default")
      (node (ref "C33") (pin "1") (pinfunction "1_1") (pintype "passive"))
      (node (ref "D9") (pin "1") (pinfunction "A_1") (pintype "passive"))
      (node (ref "PSIG") (pin "28") (pinfunction "28_28") (pintype "passive"))
      (node (ref "R55") (pin "1") (pinfunction "1_1") (pintype "passive"))
    )
    (net (code "7") (name "/HINA") (class "Default")
      (node (ref "PSIG") (pin "4") (pinfunction "4_4") (pintype "passive"))
      (node (ref "R58") (pin "1") (pinfunction "1_1") (pintype "passive"))
      (node (ref "R59") (pin "2") (pinfunction "2_2") (pintype "passive"))
    )
    (net (code "8") (name "/HINB") (class "Default")
      (node (ref "PSIG") (pin "14") (pinfunction "14_14") (pintype "passive"))
      (node (ref "R62") (pin "1") (pinfunction "1_1") (pintype "passive"))
      (node (ref "R63") (pin "2") (pinfunction "2_2") (pintype "passive"))
    )
    (net (code "9") (name "/HINC") (class "Default")
      (node (ref "PSIG") (pin "24") (pinfunction "24_24") (pintype "passive"))
      (node (ref "R66") (pin "1") (pinfunction "1_1") (pintype "passive"))
      (node (ref "R67") (pin "2") (pinfunction "2_2") (pintype "passive"))
    )
    (net (code "10") (name "/LINA") (class "Default")
      (node (ref "PSIG") (pin "2") (pinfunction "2_2") (pintype "passive"))
      (node (ref "R56") (pin "1") (pinfunction "1_1") (pintype "passive"))
      (node (ref "R57") (pin "1") (pinfunction "1_1") (pintype "passive"))
    )
    (net (code "11") (name "/LINB") (class "Default")
      (node (ref "PSIG") (pin "12") (pinfunction "12_12") (pintype "passive"))
      (node (ref "R60") (pin "1") (pinfunction "1_1") (pintype "passive"))
      (node (ref "R61") (pin "1") (pinfunction "1_1") (pintype "passive"))
    )
    (net (code "12") (name "/LINC") (class "Default")
      (node (ref "PSIG") (pin "22") (pinfunction "22_22") (pintype "passive"))
      (node (ref "R64") (pin "1") (pinfunction "1_1") (pintype "passive"))
      (node (ref "R65") (pin "1") (pinfunction "1_1") (pintype "passive"))
    )
    (net (code "13") (name "/MITTEL") (class "Default")
      (node (ref "R74") (pin "1") (pinfunction "1_1") (pintype "passive"))
      (node (ref "R75") (pin "1") (pinfunction "1_1") (pintype "passive"))
      (node (ref "R76") (pin "1") (pinfunction "1_1") (pintype "passive"))
      (node (ref "U6") (pin "4") (pinfunction "2IN-_4") (pintype "passive"))
      (node (ref "U6") (pin "6") (pinfunction "1IN-_6") (pintype "passive"))
      (node (ref "U6") (pin "8") (pinfunction "3IN-_8") (pintype "passive"))
    )
    (net (code "14") (name "/OUTA") (class "Default")
      (node (ref "C1") (pin "1") (pinfunction "1_1") (pintype "passive"))
      (node (ref "MOTOR") (pin "1") (pinfunction "1_1") (pintype "passive"))
      (node (ref "Q1") (pin "S") (pinfunction "S_S") (pintype "passive"))
      (node (ref "Q2") (pin "D") (pinfunction "D_D") (pintype "passive"))
      (node (ref "R68") (pin "2") (pinfunction "2_2") (pintype "passive"))
      (node (ref "U1") (pin "14") (pinfunction "OUT_14") (pintype "passive"))
    )
    (net (code "15") (name "/OUTB") (class "Default")
      (node (ref "C13") (pin "1") (pinfunction "1_1") (pintype "passive"))
      (node (ref "MOTOR") (pin "2") (pinfunction "2_2") (pintype "passive"))
      (node (ref "Q3") (pin "S") (pinfunction "S_S") (pintype "passive"))
      (node (ref "Q4") (pin "D") (pinfunction "D_D") (pintype "passive"))
      (node (ref "R69") (pin "2") (pinfunction "2_2") (pintype "passive"))
      (node (ref "U2") (pin "14") (pinfunction "OUT_14") (pintype "passive"))
    )
    (net (code "16") (name "/OUTC") (class "Default")
      (node (ref "C21") (pin "1") (pinfunction "1_1") (pintype "passive"))
      (node (ref "MOTOR") (pin "3") (pinfunction "3_3") (pintype "passive"))
      (node (ref "Q5") (pin "S") (pinfunction "S_S") (pintype "passive"))
      (node (ref "Q6") (pin "D") (pinfunction "D_D") (pintype "passive"))
      (node (ref "R70") (pin "2") (pinfunction "2_2") (pintype "passive"))
      (node (ref "U3") (pin "14") (pinfunction "OUT_14") (pintype "passive"))
    )
    (net (code "17") (name "/PHASE_A") (class "Default")
      (node (ref "C36") (pin "1") (pinfunction "1_1") (pintype "passive"))
      (node (ref "R68") (pin "1") (pinfunction "1_1") (pintype "passive"))
      (node (ref "R73") (pin "1") (pinfunction "1_1") (pintype "passive"))
      (node (ref "R74") (pin "2") (pinfunction "2_2") (pintype "passive"))
      (node (ref "U6") (pin "7") (pinfunction "1IN+_7") (pintype "passive"))
    )
    (net (code "18") (name "/PHASE_B") (class "Default")
      (node (ref "C35") (pin "1") (pinfunction "1_1") (pintype "passive"))
      (node (ref "R69") (pin "1") (pinfunction "1_1") (pintype "passive"))
      (node (ref "R72") (pin "1") (pinfunction "1_1") (pintype "passive"))
      (node (ref "R75") (pin "2") (pinfunction "2_2") (pintype "passive"))
      (node (ref "U6") (pin "5") (pinfunction "2IN+_5") (pintype "passive"))
    )
    (net (code "19") (name "/PHASE_C") (class "Default")
      (node (ref "C34") (pin "1") (pinfunction "1_1") (pintype "passive"))
      (node (ref "R70") (pin "1") (pinfunction "1_1") (pintype "passive"))
      (node (ref "R71") (pin "1") (pinfunction "1_1") (pintype "passive"))
      (node (ref "R76") (pin "2") (pinfunction "2_2") (pintype "passive"))
      (node (ref "U6") (pin "9") (pinfunction "3IN+_9") (pintype "passive"))
    )
    (net (code "20") (name "/SDODA") (class "Default")
      (node (ref "C3") (pin "1") (pinfunction "1_1") (pintype "passive"))
      (node (ref "PSIG") (pin "6") (pinfunction "6_6") (pintype "passive"))
      (node (ref "R1") (pin "2") (pinfunction "2_2") (pintype "passive"))
      (node (ref "U1") (pin "2") (pinfunction "_SD/OD_2") (pintype "passive"))
    )
    (net (code "21") (name "/SDODB") (class "Default")
      (node (ref "C9") (pin "1") (pinfunction "1_1") (pintype "passive"))
      (node (ref "PSIG") (pin "16") (pinfunction "16_16") (pintype "passive"))
      (node (ref "R17") (pin "2") (pinfunction "2_2") (pintype "passive"))
      (node (ref "U2") (pin "2") (pinfunction "_SD/OD_2") (pintype "passive"))
    )
    (net (code "22") (name "/SDODC") (class "Default")
      (node (ref "C17") (pin "1") (pinfunction "1_1") (pintype "passive"))
      (node (ref "PSIG") (pin "26") (pinfunction "26_26") (pintype "passive"))
      (node (ref "R33") (pin "2") (pinfunction "2_2") (pintype "passive"))
      (node (ref "U3") (pin "2") (pinfunction "_SD/OD_2") (pintype "passive"))
    )
    (net (code "23") (name "DGND") (class "Default")
      (node (ref "C10") (pin "1") (pinfunction "1_1") (pintype "passive"))
      (node (ref "C11") (pin "1") (pinfunction "1_1") (pintype "passive"))
      (node (ref "C12") (pin "1") (pinfunction "1_1") (pintype "passive"))
      (node (ref "C18") (pin "1") (pinfunction "1_1") (pintype "passive"))
      (node (ref "C19") (pin "1") (pinfunction "1_1") (pintype "passive"))
      (node (ref "C2") (pin "1") (pinfunction "1_1") (pintype "passive"))
      (node (ref "C20") (pin "1") (pinfunction "1_1") (pintype "passive"))
      (node (ref "C26") (pin "2") (pinfunction "2_2") (pintype "passive"))
      (node (ref "C4") (pin "1") (pinfunction "1_1") (pintype "passive"))
      (node (ref "C5") (pin "1") (pinfunction "1_1") (pintype "passive"))
      (node (ref "R18") (pin "1") (pinfunction "1_1") (pintype "passive"))
      (node (ref "R2") (pin "1") (pinfunction "1_1") (pintype "passive"))
      (node (ref "R34") (pin "1") (pinfunction "1_1") (pintype "passive"))
      (node (ref "R49") (pin "2") (pinfunction "2_2") (pintype "passive"))
      (node (ref "R51") (pin "1") (pinfunction "1_1") (pintype "passive"))
      (node (ref "U1") (pin "8") (pinfunction "GND_8") (pintype "passive"))
      (node (ref "U2") (pin "8") (pinfunction "GND_8") (pintype "passive"))
      (node (ref "U3") (pin "8") (pinfunction "GND_8") (pintype "passive"))
      (node (ref "U4") (pin "4") (pinfunction "0V_4") (pintype "passive"))
    )
    (net (code "24") (name "DVCC") (class "Default")
      (node (ref "C10") (pin "2") (pinfunction "2_2") (pintype "passive"))
      (node (ref "C11") (pin "2") (pinfunction "2_2") (pintype "passive"))
      (node (ref "C18") (pin "2") (pinfunction "2_2") (pintype "passive"))
      (node (ref "C19") (pin "2") (pinfunction "2_2") (pintype "passive"))
      (node (ref "C2") (pin "2") (pinfunction "2_2") (pintype "passive"))
      (node (ref "C26") (pin "1") (pinfunction "1_1") (pintype "passive"))
      (node (ref "C4") (pin "2") (pinfunction "2_2") (pintype "passive"))
      (node (ref "U1") (pin "4") (pinfunction "VCC_4") (pintype "passive"))
      (node (ref "U2") (pin "4") (pinfunction "VCC_4") (pintype "passive"))
      (node (ref "U3") (pin "4") (pinfunction "VCC_4") (pintype "passive"))
      (node (ref "U4") (pin "6") (pinfunction "+V0_6") (pintype "passive"))
    )
    (net (code "25") (name "GND") (class "Default")
      (node (ref "C25") (pin "1") (pinfunction "1_1") (pintype "passive"))
      (node (ref "C29") (pin "2") (pinfunction "2_2") (pintype "passive"))
      (node (ref "PSIG") (pin "23") (pinfunction "23_23") (pintype "passive"))
      (node (ref "PSIG") (pin "25") (pinfunction "25_25") (pintype "passive"))
      (node (ref "R49") (pin "1") (pinfunction "1_1") (pintype "passive"))
      (node (ref "R50") (pin "1") (pinfunction "1_1") (pintype "passive"))
      (node (ref "U4") (pin "2") (pinfunction "GND_2") (pintype "passive"))
      (node (ref "U5") (pin "1") (pinfunction "GND_1") (pintype "passive"))
    )
    (net (code "26") (name "IN_5V") (class "Default")
      (node (ref "C25") (pin "2") (pinfunction "2_2") (pintype "passive"))
      (node (ref "C29") (pin "1") (pinfunction "1_1") (pintype "passive"))
      (node (ref "PSIG") (pin "27") (pinfunction "27_27") (pintype "passive"))
      (node (ref "PSIG") (pin "29") (pinfunction "29_29") (pintype "passive"))
      (node (ref "U4") (pin "1") (pinfunction "Vin_1") (pintype "passive"))
      (node (ref "U5") (pin "2") (pinfunction "+Vin_2") (pintype "passive"))
    )
    (net (code "27") (name "Net-(C27-Pad2)") (class "Default")
      (node (ref "C27") (pin "2") (pinfunction "2_2") (pintype "passive"))
      (node (ref "C28") (pin "1") (pinfunction "1_1") (pintype "passive"))
    )
    (net (code "28") (name "Net-(D1-Pad1)") (class "Default")
      (node (ref "D1") (pin "1") (pinfunction "1_1") (pintype "passive"))
      (node (ref "R11") (pin "1") (pinfunction "1_1") (pintype "passive"))
    )
    (net (code "29") (name "Net-(D1-Pad2)") (class "Default")
      (node (ref "D1") (pin "2") (pinfunction "2_2") (pintype "passive"))
      (node (ref "Q1") (pin "G") (pinfunction "G_G") (pintype "passive"))
      (node (ref "R10") (pin "1") (pinfunction "1_1") (pintype "passive"))
    )
    (net (code "30") (name "Net-(D2-Pad2)") (class "Default")
      (node (ref "D2") (pin "2") (pinfunction "2_2") (pintype "passive"))
      (node (ref "R13") (pin "2") (pinfunction "2_2") (pintype "passive"))
    )
    (net (code "31") (name "Net-(D3-Pad1)") (class "Default")
      (node (ref "D3") (pin "1") (pinfunction "1_1") (pintype "passive"))
      (node (ref "R20") (pin "1") (pinfunction "1_1") (pintype "passive"))
    )
    (net (code "32") (name "Net-(D3-Pad2)") (class "Default")
      (node (ref "D3") (pin "2") (pinfunction "2_2") (pintype "passive"))
      (node (ref "Q3") (pin "G") (pinfunction "G_G") (pintype "passive"))
      (node (ref "R19") (pin "1") (pinfunction "1_1") (pintype "passive"))
    )
    (net (code "33") (name "Net-(D4-Pad2)") (class "Default")
      (node (ref "D4") (pin "2") (pinfunction "2_2") (pintype "passive"))
      (node (ref "R22") (pin "2") (pinfunction "2_2") (pintype "passive"))
    )
    (net (code "34") (name "Net-(D5-Pad1)") (class "Default")
      (node (ref "D5") (pin "1") (pinfunction "1_1") (pintype "passive"))
      (node (ref "R36") (pin "1") (pinfunction "1_1") (pintype "passive"))
    )
    (net (code "35") (name "Net-(D5-Pad2)") (class "Default")
      (node (ref "D5") (pin "2") (pinfunction "2_2") (pintype "passive"))
      (node (ref "Q5") (pin "G") (pinfunction "G_G") (pintype "passive"))
      (node (ref "R35") (pin "1") (pinfunction "1_1") (pintype "passive"))
    )
    (net (code "36") (name "Net-(D6-Pad2)") (class "Default")
      (node (ref "D6") (pin "2") (pinfunction "2_2") (pintype "passive"))
      (node (ref "R38") (pin "2") (pinfunction "2_2") (pintype "passive"))
    )
    (net (code "37") (name "Net-(Q2-PadG)") (class "Default")
      (node (ref "Q2") (pin "G") (pinfunction "G_G") (pintype "passive"))
      (node (ref "R12") (pin "1") (pinfunction "1_1") (pintype "passive"))
      (node (ref "R13") (pin "1") (pinfunction "1_1") (pintype "passive"))
    )
    (net (code "38") (name "Net-(Q2-PadS)") (class "Default")
      (node (ref "Q2") (pin "S") (pinfunction "S_S") (pintype "passive"))
      (node (ref "R14") (pin "1") (pinfunction "1_1") (pintype "passive"))
      (node (ref "R15") (pin "1") (pinfunction "1_1") (pintype "passive"))
      (node (ref "R3") (pin "1") (pinfunction "1_1") (pintype "passive"))
      (node (ref "R4") (pin "1") (pinfunction "1_1") (pintype "passive"))
      (node (ref "R5") (pin "1") (pinfunction "1_1") (pintype "passive"))
    )
    (net (code "39") (name "Net-(Q4-PadG)") (class "Default")
      (node (ref "Q4") (pin "G") (pinfunction "G_G") (pintype "passive"))
      (node (ref "R21") (pin "1") (pinfunction "1_1") (pintype "passive"))
      (node (ref "R22") (pin "1") (pinfunction "1_1") (pintype "passive"))
    )
    (net (code "40") (name "Net-(Q4-PadS)") (class "Default")
      (node (ref "Q4") (pin "S") (pinfunction "S_S") (pintype "passive"))
      (node (ref "R23") (pin "1") (pinfunction "1_1") (pintype "passive"))
      (node (ref "R25") (pin "1") (pinfunction "1_1") (pintype "passive"))
      (node (ref "R27") (pin "1") (pinfunction "1_1") (pintype "passive"))
      (node (ref "R28") (pin "1") (pinfunction "1_1") (pintype "passive"))
      (node (ref "R29") (pin "1") (pinfunction "1_1") (pintype "passive"))
    )
    (net (code "41") (name "Net-(Q6-PadG)") (class "Default")
      (node (ref "Q6") (pin "G") (pinfunction "G_G") (pintype "passive"))
      (node (ref "R37") (pin "1") (pinfunction "1_1") (pintype "passive"))
      (node (ref "R38") (pin "1") (pinfunction "1_1") (pintype "passive"))
    )
    (net (code "42") (name "Net-(Q6-PadS)") (class "Default")
      (node (ref "Q6") (pin "S") (pinfunction "S_S") (pintype "passive"))
      (node (ref "R39") (pin "1") (pinfunction "1_1") (pintype "passive"))
      (node (ref "R41") (pin "1") (pinfunction "1_1") (pintype "passive"))
      (node (ref "R43") (pin "1") (pinfunction "1_1") (pintype "passive"))
      (node (ref "R44") (pin "1") (pinfunction "1_1") (pintype "passive"))
      (node (ref "R45") (pin "1") (pinfunction "1_1") (pintype "passive"))
    )
    (net (code "43") (name "Net-(R16-Pad2)") (class "Default")
      (node (ref "R16") (pin "2") (pinfunction "2_2") (pintype "passive"))
      (node (ref "R9") (pin "1") (pinfunction "1_1") (pintype "passive"))
    )
    (net (code "44") (name "Net-(R31-Pad1)") (class "Default")
      (node (ref "R31") (pin "1") (pinfunction "1_1") (pintype "passive"))
      (node (ref "R32") (pin "2") (pinfunction "2_2") (pintype "passive"))
    )
    (net (code "45") (name "Net-(R47-Pad2)") (class "Default")
      (node (ref "R47") (pin "2") (pinfunction "2_2") (pintype "passive"))
      (node (ref "R48") (pin "1") (pinfunction "1_1") (pintype "passive"))
    )
    (net (code "46") (name "Net-(U1-BOOT)") (class "Default")
      (node (ref "C1") (pin "2") (pinfunction "2_2") (pintype "passive"))
      (node (ref "U1") (pin "16") (pinfunction "BOOT_16") (pintype "passive"))
    )
    (net (code "47") (name "Net-(U1-CP+)") (class "Default")
      (node (ref "C6") (pin "1") (pinfunction "1_1") (pintype "passive"))
      (node (ref "R3") (pin "2") (pinfunction "2_2") (pintype "passive"))
      (node (ref "U1") (pin "10") (pinfunction "CP+_10") (pintype "passive"))
    )
    (net (code "48") (name "Net-(U1-DT)") (class "Default")
      (node (ref "C5") (pin "2") (pinfunction "2_2") (pintype "passive"))
      (node (ref "R2") (pin "2") (pinfunction "2_2") (pintype "passive"))
      (node (ref "U1") (pin "5") (pinfunction "DT_5") (pintype "passive"))
    )
    (net (code "49") (name "Net-(U1-HIN)") (class "Default")
      (node (ref "R58") (pin "2") (pinfunction "2_2") (pintype "passive"))
      (node (ref "U1") (pin "3") (pinfunction "HIN_3") (pintype "passive"))
    )
    (net (code "50") (name "Net-(U1-HVG)") (class "Default")
      (node (ref "R10") (pin "2") (pinfunction "2_2") (pintype "passive"))
      (node (ref "R11") (pin "2") (pinfunction "2_2") (pintype "passive"))
      (node (ref "U1") (pin "15") (pinfunction "HVG_15") (pintype "passive"))
    )
    (net (code "51") (name "Net-(U1-LVG)") (class "Default")
      (node (ref "D2") (pin "1") (pinfunction "1_1") (pintype "passive"))
      (node (ref "R12") (pin "2") (pinfunction "2_2") (pintype "passive"))
      (node (ref "U1") (pin "11") (pinfunction "LVG_11") (pintype "passive"))
    )
    (net (code "52") (name "Net-(U1-OP+)") (class "Default")
      (node (ref "C7") (pin "1") (pinfunction "1_1") (pintype "passive"))
      (node (ref "R5") (pin "2") (pinfunction "2_2") (pintype "passive"))
      (node (ref "R6") (pin "1") (pinfunction "1_1") (pintype "passive"))
      (node (ref "R7") (pin "2") (pinfunction "2_2") (pintype "passive"))
      (node (ref "U1") (pin "9") (pinfunction "OP+_9") (pintype "passive"))
    )
    (net (code "53") (name "Net-(U1-OP-)") (class "Default")
      (node (ref "C8") (pin "2") (pinfunction "2_2") (pintype "passive"))
      (node (ref "R8") (pin "2") (pinfunction "2_2") (pintype "passive"))
      (node (ref "R9") (pin "2") (pinfunction "2_2") (pintype "passive"))
      (node (ref "U1") (pin "6") (pinfunction "OP-_6") (pintype "passive"))
    )
    (net (code "54") (name "Net-(U1-OPOUT)") (class "Default")
      (node (ref "C8") (pin "1") (pinfunction "1_1") (pintype "passive"))
      (node (ref "R16") (pin "1") (pinfunction "1_1") (pintype "passive"))
      (node (ref "R54") (pin "2") (pinfunction "2_2") (pintype "passive"))
      (node (ref "U1") (pin "7") (pinfunction "OPOUT_7") (pintype "passive"))
    )
    (net (code "55") (name "Net-(U1-_LIN)") (class "Default")
      (node (ref "R57") (pin "2") (pinfunction "2_2") (pintype "passive"))
      (node (ref "U1") (pin "1") (pinfunction "_LIN_1") (pintype "passive"))
    )
    (net (code "56") (name "Net-(U2-BOOT)") (class "Default")
      (node (ref "C13") (pin "2") (pinfunction "2_2") (pintype "passive"))
      (node (ref "U2") (pin "16") (pinfunction "BOOT_16") (pintype "passive"))
    )
    (net (code "57") (name "Net-(U2-CP+)") (class "Default")
      (node (ref "C14") (pin "1") (pinfunction "1_1") (pintype "passive"))
      (node (ref "R23") (pin "2") (pinfunction "2_2") (pintype "passive"))
      (node (ref "U2") (pin "10") (pinfunction "CP+_10") (pintype "passive"))
    )
    (net (code "58") (name "Net-(U2-DT)") (class "Default")
      (node (ref "C12") (pin "2") (pinfunction "2_2") (pintype "passive"))
      (node (ref "R18") (pin "2") (pinfunction "2_2") (pintype "passive"))
      (node (ref "U2") (pin "5") (pinfunction "DT_5") (pintype "passive"))
    )
    (net (code "59") (name "Net-(U2-HIN)") (class "Default")
      (node (ref "R62") (pin "2") (pinfunction "2_2") (pintype "passive"))
      (node (ref "U2") (pin "3") (pinfunction "HIN_3") (pintype "passive"))
    )
    (net (code "60") (name "Net-(U2-HVG)") (class "Default")
      (node (ref "R19") (pin "2") (pinfunction "2_2") (pintype "passive"))
      (node (ref "R20") (pin "2") (pinfunction "2_2") (pintype "passive"))
      (node (ref "U2") (pin "15") (pinfunction "HVG_15") (pintype "passive"))
    )
    (net (code "61") (name "Net-(U2-LVG)") (class "Default")
      (node (ref "D4") (pin "1") (pinfunction "1_1") (pintype "passive"))
      (node (ref "R21") (pin "2") (pinfunction "2_2") (pintype "passive"))
      (node (ref "U2") (pin "11") (pinfunction "LVG_11") (pintype "passive"))
    )
    (net (code "62") (name "Net-(U2-OP+)") (class "Default")
      (node (ref "C15") (pin "1") (pinfunction "1_1") (pintype "passive"))
      (node (ref "R24") (pin "1") (pinfunction "1_1") (pintype "passive"))
      (node (ref "R25") (pin "2") (pinfunction "2_2") (pintype "passive"))
      (node (ref "R26") (pin "2") (pinfunction "2_2") (pintype "passive"))
      (node (ref "U2") (pin "9") (pinfunction "OP+_9") (pintype "passive"))
    )
    (net (code "63") (name "Net-(U2-OP-)") (class "Default")
      (node (ref "C16") (pin "2") (pinfunction "2_2") (pintype "passive"))
      (node (ref "R30") (pin "2") (pinfunction "2_2") (pintype "passive"))
      (node (ref "R31") (pin "2") (pinfunction "2_2") (pintype "passive"))
      (node (ref "U2") (pin "6") (pinfunction "OP-_6") (pintype "passive"))
    )
    (net (code "64") (name "Net-(U2-OPOUT)") (class "Default")
      (node (ref "C16") (pin "1") (pinfunction "1_1") (pintype "passive"))
      (node (ref "R32") (pin "1") (pinfunction "1_1") (pintype "passive"))
      (node (ref "R53") (pin "2") (pinfunction "2_2") (pintype "passive"))
      (node (ref "U2") (pin "7") (pinfunction "OPOUT_7") (pintype "passive"))
    )
    (net (code "65") (name "Net-(U2-_LIN)") (class "Default")
      (node (ref "R61") (pin "2") (pinfunction "2_2") (pintype "passive"))
      (node (ref "U2") (pin "1") (pinfunction "_LIN_1") (pintype "passive"))
    )
    (net (code "66") (name "Net-(U3-BOOT)") (class "Default")
      (node (ref "C21") (pin "2") (pinfunction "2_2") (pintype "passive"))
      (node (ref "U3") (pin "16") (pinfunction "BOOT_16") (pintype "passive"))
    )
    (net (code "67") (name "Net-(U3-CP+)") (class "Default")
      (node (ref "C22") (pin "1") (pinfunction "1_1") (pintype "passive"))
      (node (ref "R39") (pin "2") (pinfunction "2_2") (pintype "passive"))
      (node (ref "U3") (pin "10") (pinfunction "CP+_10") (pintype "passive"))
    )
    (net (code "68") (name "Net-(U3-DT)") (class "Default")
      (node (ref "C20") (pin "2") (pinfunction "2_2") (pintype "passive"))
      (node (ref "R34") (pin "2") (pinfunction "2_2") (pintype "passive"))
      (node (ref "U3") (pin "5") (pinfunction "DT_5") (pintype "passive"))
    )
    (net (code "69") (name "Net-(U3-HIN)") (class "Default")
      (node (ref "R66") (pin "2") (pinfunction "2_2") (pintype "passive"))
      (node (ref "U3") (pin "3") (pinfunction "HIN_3") (pintype "passive"))
    )
    (net (code "70") (name "Net-(U3-HVG)") (class "Default")
      (node (ref "R35") (pin "2") (pinfunction "2_2") (pintype "passive"))
      (node (ref "R36") (pin "2") (pinfunction "2_2") (pintype "passive"))
      (node (ref "U3") (pin "15") (pinfunction "HVG_15") (pintype "passive"))
    )
    (net (code "71") (name "Net-(U3-LVG)") (class "Default")
      (node (ref "D6") (pin "1") (pinfunction "1_1") (pintype "passive"))
      (node (ref "R37") (pin "2") (pinfunction "2_2") (pintype "passive"))
      (node (ref "U3") (pin "11") (pinfunction "LVG_11") (pintype "passive"))
    )
    (net (code "72") (name "Net-(U3-OP+)") (class "Default")
      (node (ref "C23") (pin "1") (pinfunction "1_1") (pintype "passive"))
      (node (ref "R40") (pin "1") (pinfunction "1_1") (pintype "passive"))
      (node (ref "R41") (pin "2") (pinfunction "2_2") (pintype "passive"))
      (node (ref "R42") (pin "2") (pinfunction "2_2") (pintype "passive"))
      (node (ref "U3") (pin "9") (pinfunction "OP+_9") (pintype "passive"))
    )
    (net (code "73") (name "Net-(U3-OP-)") (class "Default")
      (node (ref "C24") (pin "2") (pinfunction "2_2") (pintype "passive"))
      (node (ref "R46") (pin "2") (pinfunction "2_2") (pintype "passive"))
      (node (ref "R48") (pin "2") (pinfunction "2_2") (pintype "passive"))
      (node (ref "U3") (pin "6") (pinfunction "OP-_6") (pintype "passive"))
    )
    (net (code "74") (name "Net-(U3-OPOUT)") (class "Default")
      (node (ref "C24") (pin "1") (pinfunction "1_1") (pintype "passive"))
      (node (ref "R47") (pin "1") (pinfunction "1_1") (pintype "passive"))
      (node (ref "R55") (pin "2") (pinfunction "2_2") (pintype "passive"))
      (node (ref "U3") (pin "7") (pinfunction "OPOUT_7") (pintype "passive"))
    )
    (net (code "75") (name "Net-(U3-_LIN)") (class "Default")
      (node (ref "R65") (pin "2") (pinfunction "2_2") (pintype "passive"))
      (node (ref "U3") (pin "1") (pinfunction "_LIN_1") (pintype "passive"))
    )
    (net (code "76") (name "PGND") (class "Default")
      (node (ref "C14") (pin "2") (pinfunction "2_2") (pintype "passive"))
      (node (ref "C22") (pin "2") (pinfunction "2_2") (pintype "passive"))
      (node (ref "C28") (pin "2") (pinfunction "2_2") (pintype "passive"))
      (node (ref "C34") (pin "2") (pinfunction "2_2") (pintype "passive"))
      (node (ref "C35") (pin "2") (pinfunction "2_2") (pintype "passive"))
      (node (ref "C36") (pin "2") (pinfunction "2_2") (pintype "passive"))
      (node (ref "C6") (pin "2") (pinfunction "2_2") (pintype "passive"))
      (node (ref "P1") (pin "1") (pinfunction "1_1") (pintype "passive"))
      (node (ref "R14") (pin "2") (pinfunction "2_2") (pintype "passive"))
      (node (ref "R15") (pin "2") (pinfunction "2_2") (pintype "passive"))
      (node (ref "R27") (pin "2") (pinfunction "2_2") (pintype "passive"))
      (node (ref "R28") (pin "2") (pinfunction "2_2") (pintype "passive"))
      (node (ref "R29") (pin "2") (pinfunction "2_2") (pintype "passive"))
      (node (ref "R30") (pin "1") (pinfunction "1_1") (pintype "passive"))
      (node (ref "R4") (pin "2") (pinfunction "2_2") (pintype "passive"))
      (node (ref "R43") (pin "2") (pinfunction "2_2") (pintype "passive"))
      (node (ref "R44") (pin "2") (pinfunction "2_2") (pintype "passive"))
      (node (ref "R45") (pin "2") (pinfunction "2_2") (pintype "passive"))
      (node (ref "R46") (pin "1") (pinfunction "1_1") (pintype "passive"))
      (node (ref "R51") (pin "2") (pinfunction "2_2") (pintype "passive"))
      (node (ref "R71") (pin "2") (pinfunction "2_2") (pintype "passive"))
      (node (ref "R72") (pin "2") (pinfunction "2_2") (pintype "passive"))
      (node (ref "R73") (pin "2") (pinfunction "2_2") (pintype "passive"))
      (node (ref "R8") (pin "1") (pinfunction "1_1") (pintype "passive"))
    )
    (net (code "77") (name "PVCC") (class "Default")
      (node (ref "C27") (pin "1") (pinfunction "1_1") (pintype "passive"))
      (node (ref "P1") (pin "2") (pinfunction "2_2") (pintype "passive"))
      (node (ref "Q1") (pin "D") (pinfunction "D_D") (pintype "passive"))
      (node (ref "Q3") (pin "D") (pinfunction "D_D") (pintype "passive"))
      (node (ref "Q5") (pin "D") (pinfunction "D_D") (pintype "passive"))
    )
    (net (code "78") (name "SGND") (class "Default")
      (node (ref "C15") (pin "2") (pinfunction "2_2") (pintype "passive"))
      (node (ref "C17") (pin "2") (pinfunction "2_2") (pintype "passive"))
      (node (ref "C23") (pin "2") (pinfunction "2_2") (pintype "passive"))
      (node (ref "C3") (pin "2") (pinfunction "2_2") (pintype "passive"))
      (node (ref "C30") (pin "2") (pinfunction "2_2") (pintype "passive"))
      (node (ref "C31") (pin "2") (pinfunction "2_2") (pintype "passive"))
      (node (ref "C32") (pin "2") (pinfunction "2_2") (pintype "passive"))
      (node (ref "C33") (pin "2") (pinfunction "2_2") (pintype "passive"))
      (node (ref "C37") (pin "1") (pinfunction "1_1") (pintype "passive"))
      (node (ref "C7") (pin "2") (pinfunction "2_2") (pintype "passive"))
      (node (ref "C9") (pin "2") (pinfunction "2_2") (pintype "passive"))
      (node (ref "R26") (pin "1") (pinfunction "1_1") (pintype "passive"))
      (node (ref "R42") (pin "1") (pinfunction "1_1") (pintype "passive"))
      (node (ref "R50") (pin "2") (pinfunction "2_2") (pintype "passive"))
      (node (ref "R59") (pin "1") (pinfunction "1_1") (pintype "passive"))
      (node (ref "R63") (pin "1") (pinfunction "1_1") (pintype "passive"))
      (node (ref "R67") (pin "1") (pinfunction "1_1") (pintype "passive"))
      (node (ref "R7") (pin "1") (pinfunction "1_1") (pintype "passive"))
      (node (ref "U5") (pin "3") (pinfunction "-Vo_3") (pintype "passive"))
      (node (ref "U6") (pin "12") (pinfunction "GND_12") (pintype "passive"))
    )
    (net (code "79") (name "SVCC") (class "Default")
      (node (ref "C30") (pin "1") (pinfunction "1_1") (pintype "passive"))
      (node (ref "C37") (pin "2") (pinfunction "2_2") (pintype "passive"))
      (node (ref "D7") (pin "2") (pinfunction "K_2") (pintype "passive"))
      (node (ref "D8") (pin "2") (pinfunction "K_2") (pintype "passive"))
      (node (ref "D9") (pin "2") (pinfunction "K_2") (pintype "passive"))
      (node (ref "R1") (pin "1") (pinfunction "1_1") (pintype "passive"))
      (node (ref "R17") (pin "1") (pinfunction "1_1") (pintype "passive"))
      (node (ref "R24") (pin "2") (pinfunction "2_2") (pintype "passive"))
      (node (ref "R33") (pin "1") (pinfunction "1_1") (pintype "passive"))
      (node (ref "R40") (pin "2") (pinfunction "2_2") (pintype "passive"))
      (node (ref "R56") (pin "2") (pinfunction "2_2") (pintype "passive"))
      (node (ref "R6") (pin "2") (pinfunction "2_2") (pintype "passive"))
      (node (ref "R60") (pin "2") (pinfunction "2_2") (pintype "passive"))
      (node (ref "R64") (pin "2") (pinfunction "2_2") (pintype "passive"))
      (node (ref "U5") (pin "4") (pinfunction "+Vo_4") (pintype "passive"))
      (node (ref "U6") (pin "3") (pinfunction "VCC_3") (pintype "passive"))
    )
    (net (code "80") (name "unconnected-(PSIG-Pad7)") (class "Default")
      (node (ref "PSIG") (pin "7") (pinfunction "7_7") (pintype "passive"))
    )
    (net (code "81") (name "unconnected-(PSIG-Pad9)") (class "Default")
      (node (ref "PSIG") (pin "9") (pinfunction "9_9") (pintype "passive"))
    )
    (net (code "82") (name "unconnected-(PSIG-Pad10)") (class "Default")
      (node (ref "PSIG") (pin "10") (pinfunction "10_10") (pintype "passive"))
    )
    (net (code "83") (name "unconnected-(PSIG-Pad11)") (class "Default")
      (node (ref "PSIG") (pin "11") (pinfunction "11_11") (pintype "passive"))
    )
    (net (code "84") (name "unconnected-(PSIG-Pad13)") (class "Default")
      (node (ref "PSIG") (pin "13") (pinfunction "13_13") (pintype "passive"))
    )
    (net (code "85") (name "unconnected-(PSIG-Pad15)") (class "Default")
      (node (ref "PSIG") (pin "15") (pinfunction "15_15") (pintype "passive"))
    )
    (net (code "86") (name "unconnected-(PSIG-Pad17)") (class "Default")
      (node (ref "PSIG") (pin "17") (pinfunction "17_17") (pintype "passive"))
    )
    (net (code "87") (name "unconnected-(PSIG-Pad19)") (class "Default")
      (node (ref "PSIG") (pin "19") (pinfunction "19_19") (pintype "passive"))
    )
    (net (code "88") (name "unconnected-(PSIG-Pad20)") (class "Default")
      (node (ref "PSIG") (pin "20") (pinfunction "20_20") (pintype "passive"))
    )
    (net (code "89") (name "unconnected-(PSIG-Pad21)") (class "Default")
      (node (ref "PSIG") (pin "21") (pinfunction "21_21") (pintype "passive"))
    )
    (net (code "90") (name "unconnected-(PSIG-Pad30)") (class "Default")
      (node (ref "PSIG") (pin "30") (pinfunction "30_30") (pintype "passive"))
    )
    (net (code "91") (name "unconnected-(U1-NC-Pad12)") (class "Default")
      (node (ref "U1") (pin "12") (pinfunction "NC_12") (pintype "passive+no_connect"))
    )
    (net (code "92") (name "unconnected-(U1-NC-Pad13)") (class "Default")
      (node (ref "U1") (pin "13") (pinfunction "NC_13") (pintype "passive+no_connect"))
    )
    (net (code "93") (name "unconnected-(U2-NC-Pad12)") (class "Default")
      (node (ref "U2") (pin "12") (pinfunction "NC_12") (pintype "passive+no_connect"))
    )
    (net (code "94") (name "unconnected-(U2-NC-Pad13)") (class "Default")
      (node (ref "U2") (pin "13") (pinfunction "NC_13") (pintype "passive+no_connect"))
    )
    (net (code "95") (name "unconnected-(U3-NC-Pad12)") (class "Default")
      (node (ref "U3") (pin "12") (pinfunction "NC_12") (pintype "passive+no_connect"))
    )
    (net (code "96") (name "unconnected-(U3-NC-Pad13)") (class "Default")
      (node (ref "U3") (pin "13") (pinfunction "NC_13") (pintype "passive+no_connect"))
    )
    (net (code "97") (name "unconnected-(U6-4IN+-Pad11)") (class "Default")
      (node (ref "U6") (pin "11") (pinfunction "4IN+_11") (pintype "passive"))
    )
    (net (code "98") (name "unconnected-(U6-4IN--Pad10)") (class "Default")
      (node (ref "U6") (pin "10") (pinfunction "4IN-_10") (pintype "passive"))
    )
    (net (code "99") (name "unconnected-(U6-OUT4-Pad13)") (class "Default")
      (node (ref "U6") (pin "13") (pinfunction "OUT4_13") (pintype "passive"))
    )
  )
)
